# final_commit.net
KiCad netlist of a schematic drawn in EAGLE
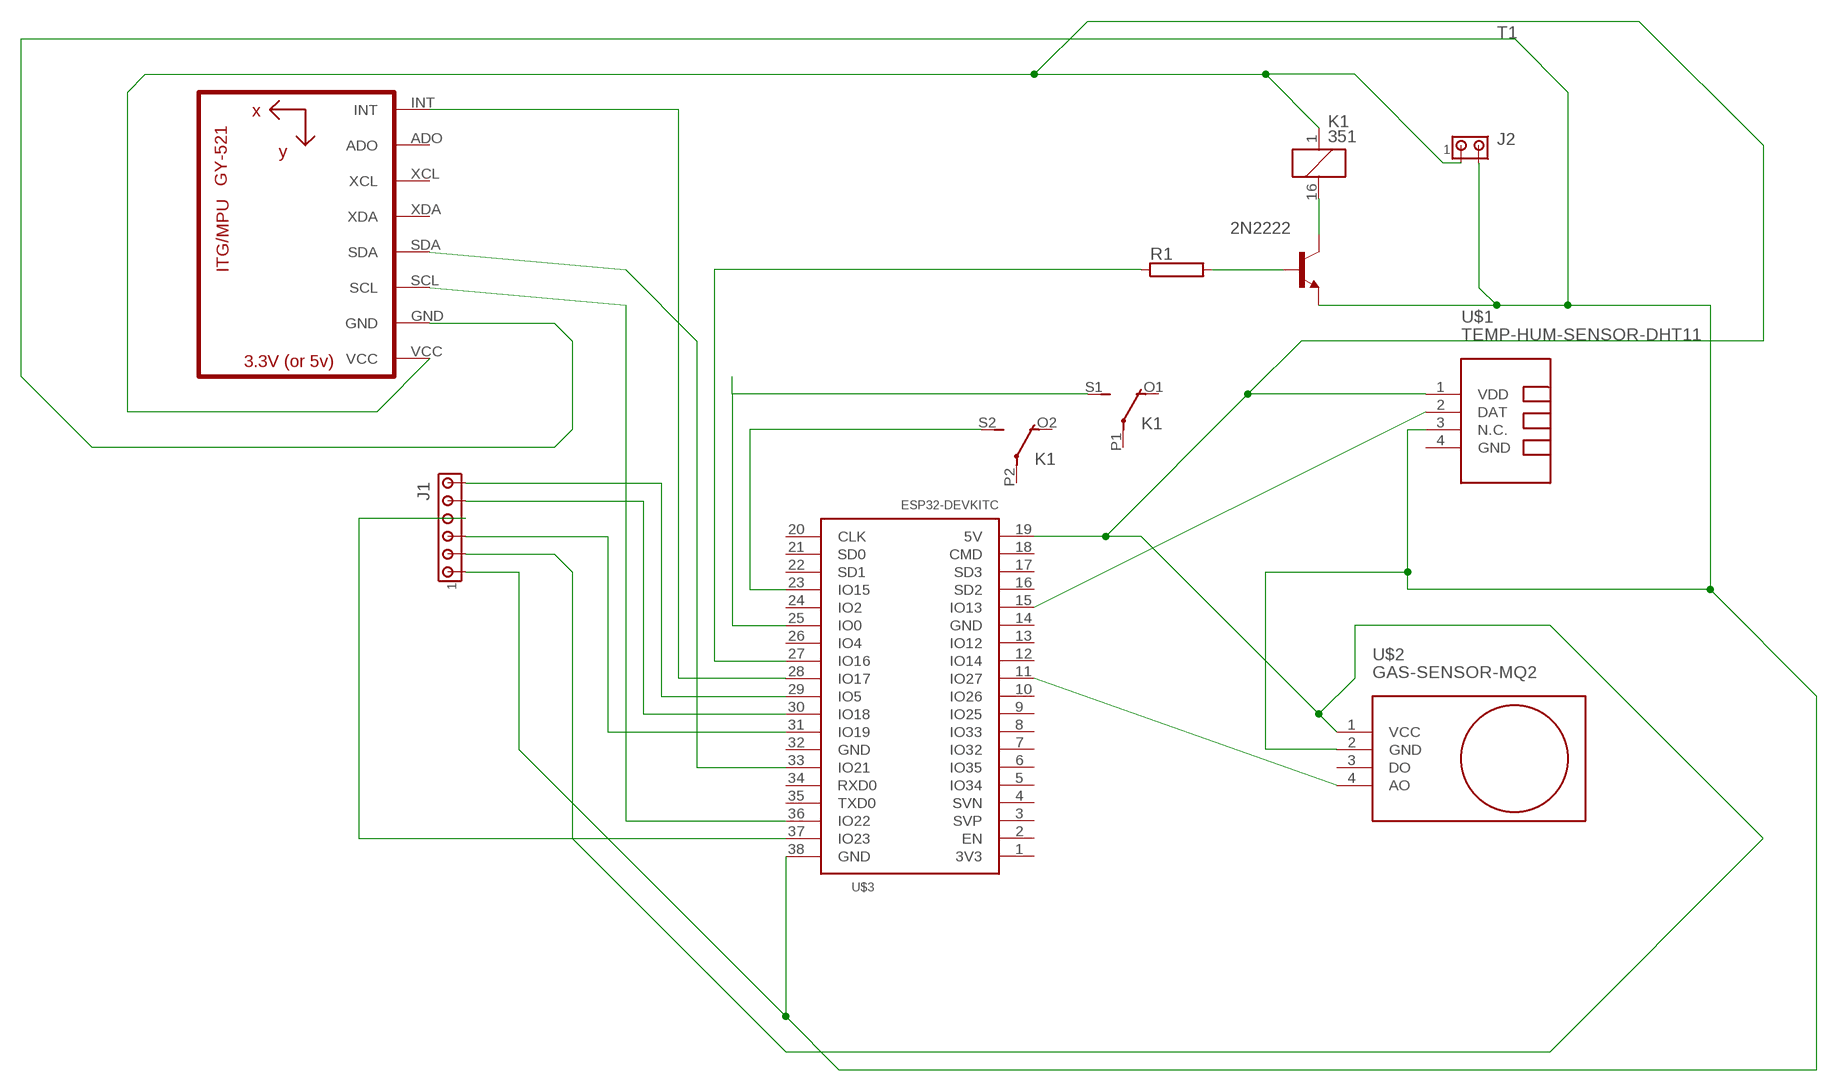
[diagram p0: schematic, sheet 1]

(export (version "E")
  (design (tool "Eeschema 10.0.6"))
  (components
    (comp (ref "J1")
      (value "MTA06-100")
      (footprint "eagle-import:10X06MTA")
      (libsource (lib "eagle-import") (part "MTA06-100"))
    )
    (comp (ref "J2")
      (value "MTA02-100")
      (footprint "eagle-import:10X02MTA")
      (libsource (lib "eagle-import") (part "MTA02-100"))
    )
    (comp (ref "K1")
      (value "351")
      (footprint "eagle-import:351")
      (libsource (lib "eagle-import") (part "351"))
    )
    (comp (ref "R1")
      (value "RMG100-V")
      (footprint "eagle-import:TO-247-2V")
      (libsource (lib "eagle-import") (part "RMG100-V"))
    )
    (comp (ref "T1")
      (value "2N2222")
      (footprint "eagle-import:TO18")
      (libsource (lib "eagle-import") (part "2N2222"))
    )
    (comp (ref "U$1")
      (value "TEMP-HUM-SENSOR-DHT11")
      (footprint "eagle-import:TEMP-HUM-SENSOR-DHT11")
      (libsource (lib "eagle-import") (part "TEMP-HUM-SENSOR-DHT11"))
    )
    (comp (ref "U$2")
      (value "GAS-SENSOR-MQ2")
      (footprint "eagle-import:GAS-SENSOR-MQ2")
      (libsource (lib "eagle-import") (part "GAS-SENSOR-MQ2"))
    )
    (comp (ref "U$3")
      (value "ESP32DEVKITC")
      (footprint "eagle-import:ESP32-DEVKITC")
      (libsource (lib "eagle-import") (part "ESP32DEVKITC"))
    )
    (comp (ref "U2")
      (value "GY-521MPU6050")
      (footprint "eagle-import:GY-521")
      (libsource (lib "eagle-import") (part "GY-521MPU6050"))
    )
  )
  (nets
    (net (code "1") (name "/GND") (class "Default")
      (node (ref "U$1") (pin "4") (pinfunction "GND_4") (pintype "power_in"))
    )
    (net (code "2") (name "Net-(K1A-2)") (class "Default")
      (node (ref "K1") (pin "16") (pinfunction "2_16") (pintype "passive"))
      (node (ref "T1") (pin "3") (pinfunction "C_3") (pintype "passive"))
    )
    (net (code "3") (name "Net-(K1B-S)") (class "Default")
      (node (ref "K1") (pin "S1") (pinfunction "S_S1") (pintype "passive"))
      (node (ref "U$3") (pin "25") (pinfunction "IO0_25") (pintype "bidirectional"))
    )
    (net (code "4") (name "Net-(K1C-S)") (class "Default")
      (node (ref "K1") (pin "S2") (pinfunction "S_S2") (pintype "passive"))
      (node (ref "U$3") (pin "23") (pinfunction "IO15_23") (pintype "bidirectional"))
    )
    (net (code "5") (name "Net-(T1-B)") (class "Default")
      (node (ref "R1") (pin "2") (pinfunction "2_2") (pintype "passive"))
      (node (ref "T1") (pin "2") (pinfunction "B_2") (pintype "passive"))
    )
    (net (code "6") (name "Net-(T1-E)") (class "Default")
      (node (ref "J1") (pin "1") (pinfunction "1_1") (pintype "passive"))
      (node (ref "J2") (pin "2") (pinfunction "2_2") (pintype "passive"))
      (node (ref "T1") (pin "1") (pinfunction "E_1") (pintype "passive"))
      (node (ref "U$1") (pin "3") (pinfunction "N.C._3") (pintype "passive"))
      (node (ref "U$2") (pin "2") (pinfunction "GND_2") (pintype "power_in"))
      (node (ref "U$3") (pin "38") (pinfunction "GND_38") (pintype "bidirectional"))
      (node (ref "U2") (pin "GND") (pinfunction "GND_GND") (pintype "bidirectional"))
    )
    (net (code "7") (name "Net-(U$1-DAT)") (class "Default")
      (node (ref "U$1") (pin "2") (pinfunction "DAT_2") (pintype "bidirectional"))
      (node (ref "U$3") (pin "15") (pinfunction "IO13_15") (pintype "bidirectional"))
    )
    (net (code "8") (name "Net-(U$1-VDD)") (class "Default")
      (node (ref "J1") (pin "2") (pinfunction "2_2") (pintype "passive"))
      (node (ref "J2") (pin "1") (pinfunction "1_1") (pintype "passive"))
      (node (ref "K1") (pin "1") (pinfunction "1_1") (pintype "passive"))
      (node (ref "U$1") (pin "1") (pinfunction "VDD_1") (pintype "power_in"))
      (node (ref "U$2") (pin "1") (pinfunction "VCC_1") (pintype "power_in"))
      (node (ref "U$3") (pin "19") (pinfunction "5V_19") (pintype "bidirectional"))
      (node (ref "U2") (pin "VCC") (pinfunction "VCC_VCC") (pintype "bidirectional"))
    )
    (net (code "9") (name "Net-(U$2-AO)") (class "Default")
      (node (ref "U$2") (pin "4") (pinfunction "AO_4") (pintype "output"))
      (node (ref "U$3") (pin "11") (pinfunction "IO27_11") (pintype "bidirectional"))
    )
    (net (code "10") (name "Net-(U$3-IO5)") (class "Default")
      (node (ref "J1") (pin "6") (pinfunction "6_6") (pintype "passive"))
      (node (ref "U$3") (pin "29") (pinfunction "IO5_29") (pintype "bidirectional"))
    )
    (net (code "11") (name "Net-(U$3-IO16)") (class "Default")
      (node (ref "R1") (pin "1") (pinfunction "1_1") (pintype "passive"))
      (node (ref "U$3") (pin "27") (pinfunction "IO16_27") (pintype "bidirectional"))
    )
    (net (code "12") (name "Net-(U$3-IO17)") (class "Default")
      (node (ref "U$3") (pin "28") (pinfunction "IO17_28") (pintype "bidirectional"))
      (node (ref "U2") (pin "INT") (pinfunction "INT_INT") (pintype "bidirectional"))
    )
    (net (code "13") (name "Net-(U$3-IO18)") (class "Default")
      (node (ref "J1") (pin "5") (pinfunction "5_5") (pintype "passive"))
      (node (ref "U$3") (pin "30") (pinfunction "IO18_30") (pintype "bidirectional"))
    )
    (net (code "14") (name "Net-(U$3-IO19)") (class "Default")
      (node (ref "J1") (pin "3") (pinfunction "3_3") (pintype "passive"))
      (node (ref "U$3") (pin "31") (pinfunction "IO19_31") (pintype "bidirectional"))
    )
    (net (code "15") (name "Net-(U$3-IO21)") (class "Default")
      (node (ref "U$3") (pin "33") (pinfunction "IO21_33") (pintype "bidirectional"))
      (node (ref "U2") (pin "SDA") (pinfunction "SDA_SDA") (pintype "bidirectional"))
    )
    (net (code "16") (name "Net-(U$3-IO22)") (class "Default")
      (node (ref "U$3") (pin "36") (pinfunction "IO22_36") (pintype "bidirectional"))
      (node (ref "U2") (pin "SCL") (pinfunction "SCL_SCL") (pintype "bidirectional"))
    )
    (net (code "17") (name "Net-(U$3-IO23)") (class "Default")
      (node (ref "J1") (pin "4") (pinfunction "4_4") (pintype "passive"))
      (node (ref "U$3") (pin "37") (pinfunction "IO23_37") (pintype "bidirectional"))
    )
    (net (code "18") (name "unconnected-(K1B-O-PadO1)") (class "Default")
      (node (ref "K1") (pin "O1") (pinfunction "O_O1") (pintype "passive"))
    )
    (net (code "19") (name "unconnected-(K1B-P-PadP1)") (class "Default")
      (node (ref "K1") (pin "P1") (pinfunction "P_P1") (pintype "passive"))
    )
    (net (code "20") (name "unconnected-(K1C-O-PadO2)") (class "Default")
      (node (ref "K1") (pin "O2") (pinfunction "O_O2") (pintype "passive"))
    )
    (net (code "21") (name "unconnected-(K1C-P-PadP2)") (class "Default")
      (node (ref "K1") (pin "P2") (pinfunction "P_P2") (pintype "passive"))
    )
    (net (code "22") (name "unconnected-(U$2-DO-Pad3)") (class "Default")
      (node (ref "U$2") (pin "3") (pinfunction "DO_3") (pintype "output"))
    )
    (net (code "23") (name "unconnected-(U$3-3V3-Pad1)") (class "Default")
      (node (ref "U$3") (pin "1") (pinfunction "3V3_1") (pintype "bidirectional"))
    )
    (net (code "24") (name "unconnected-(U$3-CLK-Pad20)") (class "Default")
      (node (ref "U$3") (pin "20") (pinfunction "CLK_20") (pintype "bidirectional"))
    )
    (net (code "25") (name "unconnected-(U$3-CMD-Pad18)") (class "Default")
      (node (ref "U$3") (pin "18") (pinfunction "CMD_18") (pintype "bidirectional"))
    )
    (net (code "26") (name "unconnected-(U$3-EN-Pad2)") (class "Default")
      (node (ref "U$3") (pin "2") (pinfunction "EN_2") (pintype "bidirectional"))
    )
    (net (code "27") (name "unconnected-(U$3-GND-Pad14)") (class "Default")
      (node (ref "U$3") (pin "14") (pinfunction "GND_14") (pintype "bidirectional"))
    )
    (net (code "28") (name "unconnected-(U$3-GND-Pad32)") (class "Default")
      (node (ref "U$3") (pin "32") (pinfunction "GND_32") (pintype "bidirectional"))
    )
    (net (code "29") (name "unconnected-(U$3-IO2-Pad24)") (class "Default")
      (node (ref "U$3") (pin "24") (pinfunction "IO2_24") (pintype "bidirectional"))
    )
    (net (code "30") (name "unconnected-(U$3-IO4-Pad26)") (class "Default")
      (node (ref "U$3") (pin "26") (pinfunction "IO4_26") (pintype "bidirectional"))
    )
    (net (code "31") (name "unconnected-(U$3-IO12-Pad13)") (class "Default")
      (node (ref "U$3") (pin "13") (pinfunction "IO12_13") (pintype "bidirectional"))
    )
    (net (code "32") (name "unconnected-(U$3-IO14-Pad12)") (class "Default")
      (node (ref "U$3") (pin "12") (pinfunction "IO14_12") (pintype "bidirectional"))
    )
    (net (code "33") (name "unconnected-(U$3-IO25-Pad9)") (class "Default")
      (node (ref "U$3") (pin "9") (pinfunction "IO25_9") (pintype "bidirectional"))
    )
    (net (code "34") (name "unconnected-(U$3-IO26-Pad10)") (class "Default")
      (node (ref "U$3") (pin "10") (pinfunction "IO26_10") (pintype "bidirectional"))
    )
    (net (code "35") (name "unconnected-(U$3-IO32-Pad7)") (class "Default")
      (node (ref "U$3") (pin "7") (pinfunction "IO32_7") (pintype "bidirectional"))
    )
    (net (code "36") (name "unconnected-(U$3-IO33-Pad8)") (class "Default")
      (node (ref "U$3") (pin "8") (pinfunction "IO33_8") (pintype "bidirectional"))
    )
    (net (code "37") (name "unconnected-(U$3-IO34-Pad5)") (class "Default")
      (node (ref "U$3") (pin "5") (pinfunction "IO34_5") (pintype "bidirectional"))
    )
    (net (code "38") (name "unconnected-(U$3-IO35-Pad6)") (class "Default")
      (node (ref "U$3") (pin "6") (pinfunction "IO35_6") (pintype "bidirectional"))
    )
    (net (code "39") (name "unconnected-(U$3-RXD0-Pad34)") (class "Default")
      (node (ref "U$3") (pin "34") (pinfunction "RXD0_34") (pintype "bidirectional"))
    )
    (net (code "40") (name "unconnected-(U$3-SD0-Pad21)") (class "Default")
      (node (ref "U$3") (pin "21") (pinfunction "SD0_21") (pintype "bidirectional"))
    )
    (net (code "41") (name "unconnected-(U$3-SD1-Pad22)") (class "Default")
      (node (ref "U$3") (pin "22") (pinfunction "SD1_22") (pintype "bidirectional"))
    )
    (net (code "42") (name "unconnected-(U$3-SD2-Pad16)") (class "Default")
      (node (ref "U$3") (pin "16") (pinfunction "SD2_16") (pintype "bidirectional"))
    )
    (net (code "43") (name "unconnected-(U$3-SD3-Pad17)") (class "Default")
      (node (ref "U$3") (pin "17") (pinfunction "SD3_17") (pintype "bidirectional"))
    )
    (net (code "44") (name "unconnected-(U$3-SVN-Pad4)") (class "Default")
      (node (ref "U$3") (pin "4") (pinfunction "SVN_4") (pintype "bidirectional"))
    )
    (net (code "45") (name "unconnected-(U$3-SVP-Pad3)") (class "Default")
      (node (ref "U$3") (pin "3") (pinfunction "SVP_3") (pintype "bidirectional"))
    )
    (net (code "46") (name "unconnected-(U$3-TXD0-Pad35)") (class "Default")
      (node (ref "U$3") (pin "35") (pinfunction "TXD0_35") (pintype "bidirectional"))
    )
    (net (code "47") (name "unconnected-(U2-PadADO)") (class "Default")
      (node (ref "U2") (pin "ADO") (pinfunction "ADO_ADO") (pintype "bidirectional"))
    )
    (net (code "48") (name "unconnected-(U2-PadXCL)") (class "Default")
      (node (ref "U2") (pin "XCL") (pinfunction "XCL_XCL") (pintype "bidirectional"))
    )
    (net (code "49") (name "unconnected-(U2-PadXDA)") (class "Default")
      (node (ref "U2") (pin "XDA") (pinfunction "XDA_XDA") (pintype "bidirectional"))
    )
  )
)
